# design.net
KiCad netlist of a schematic drawn in EasyEDA Pro
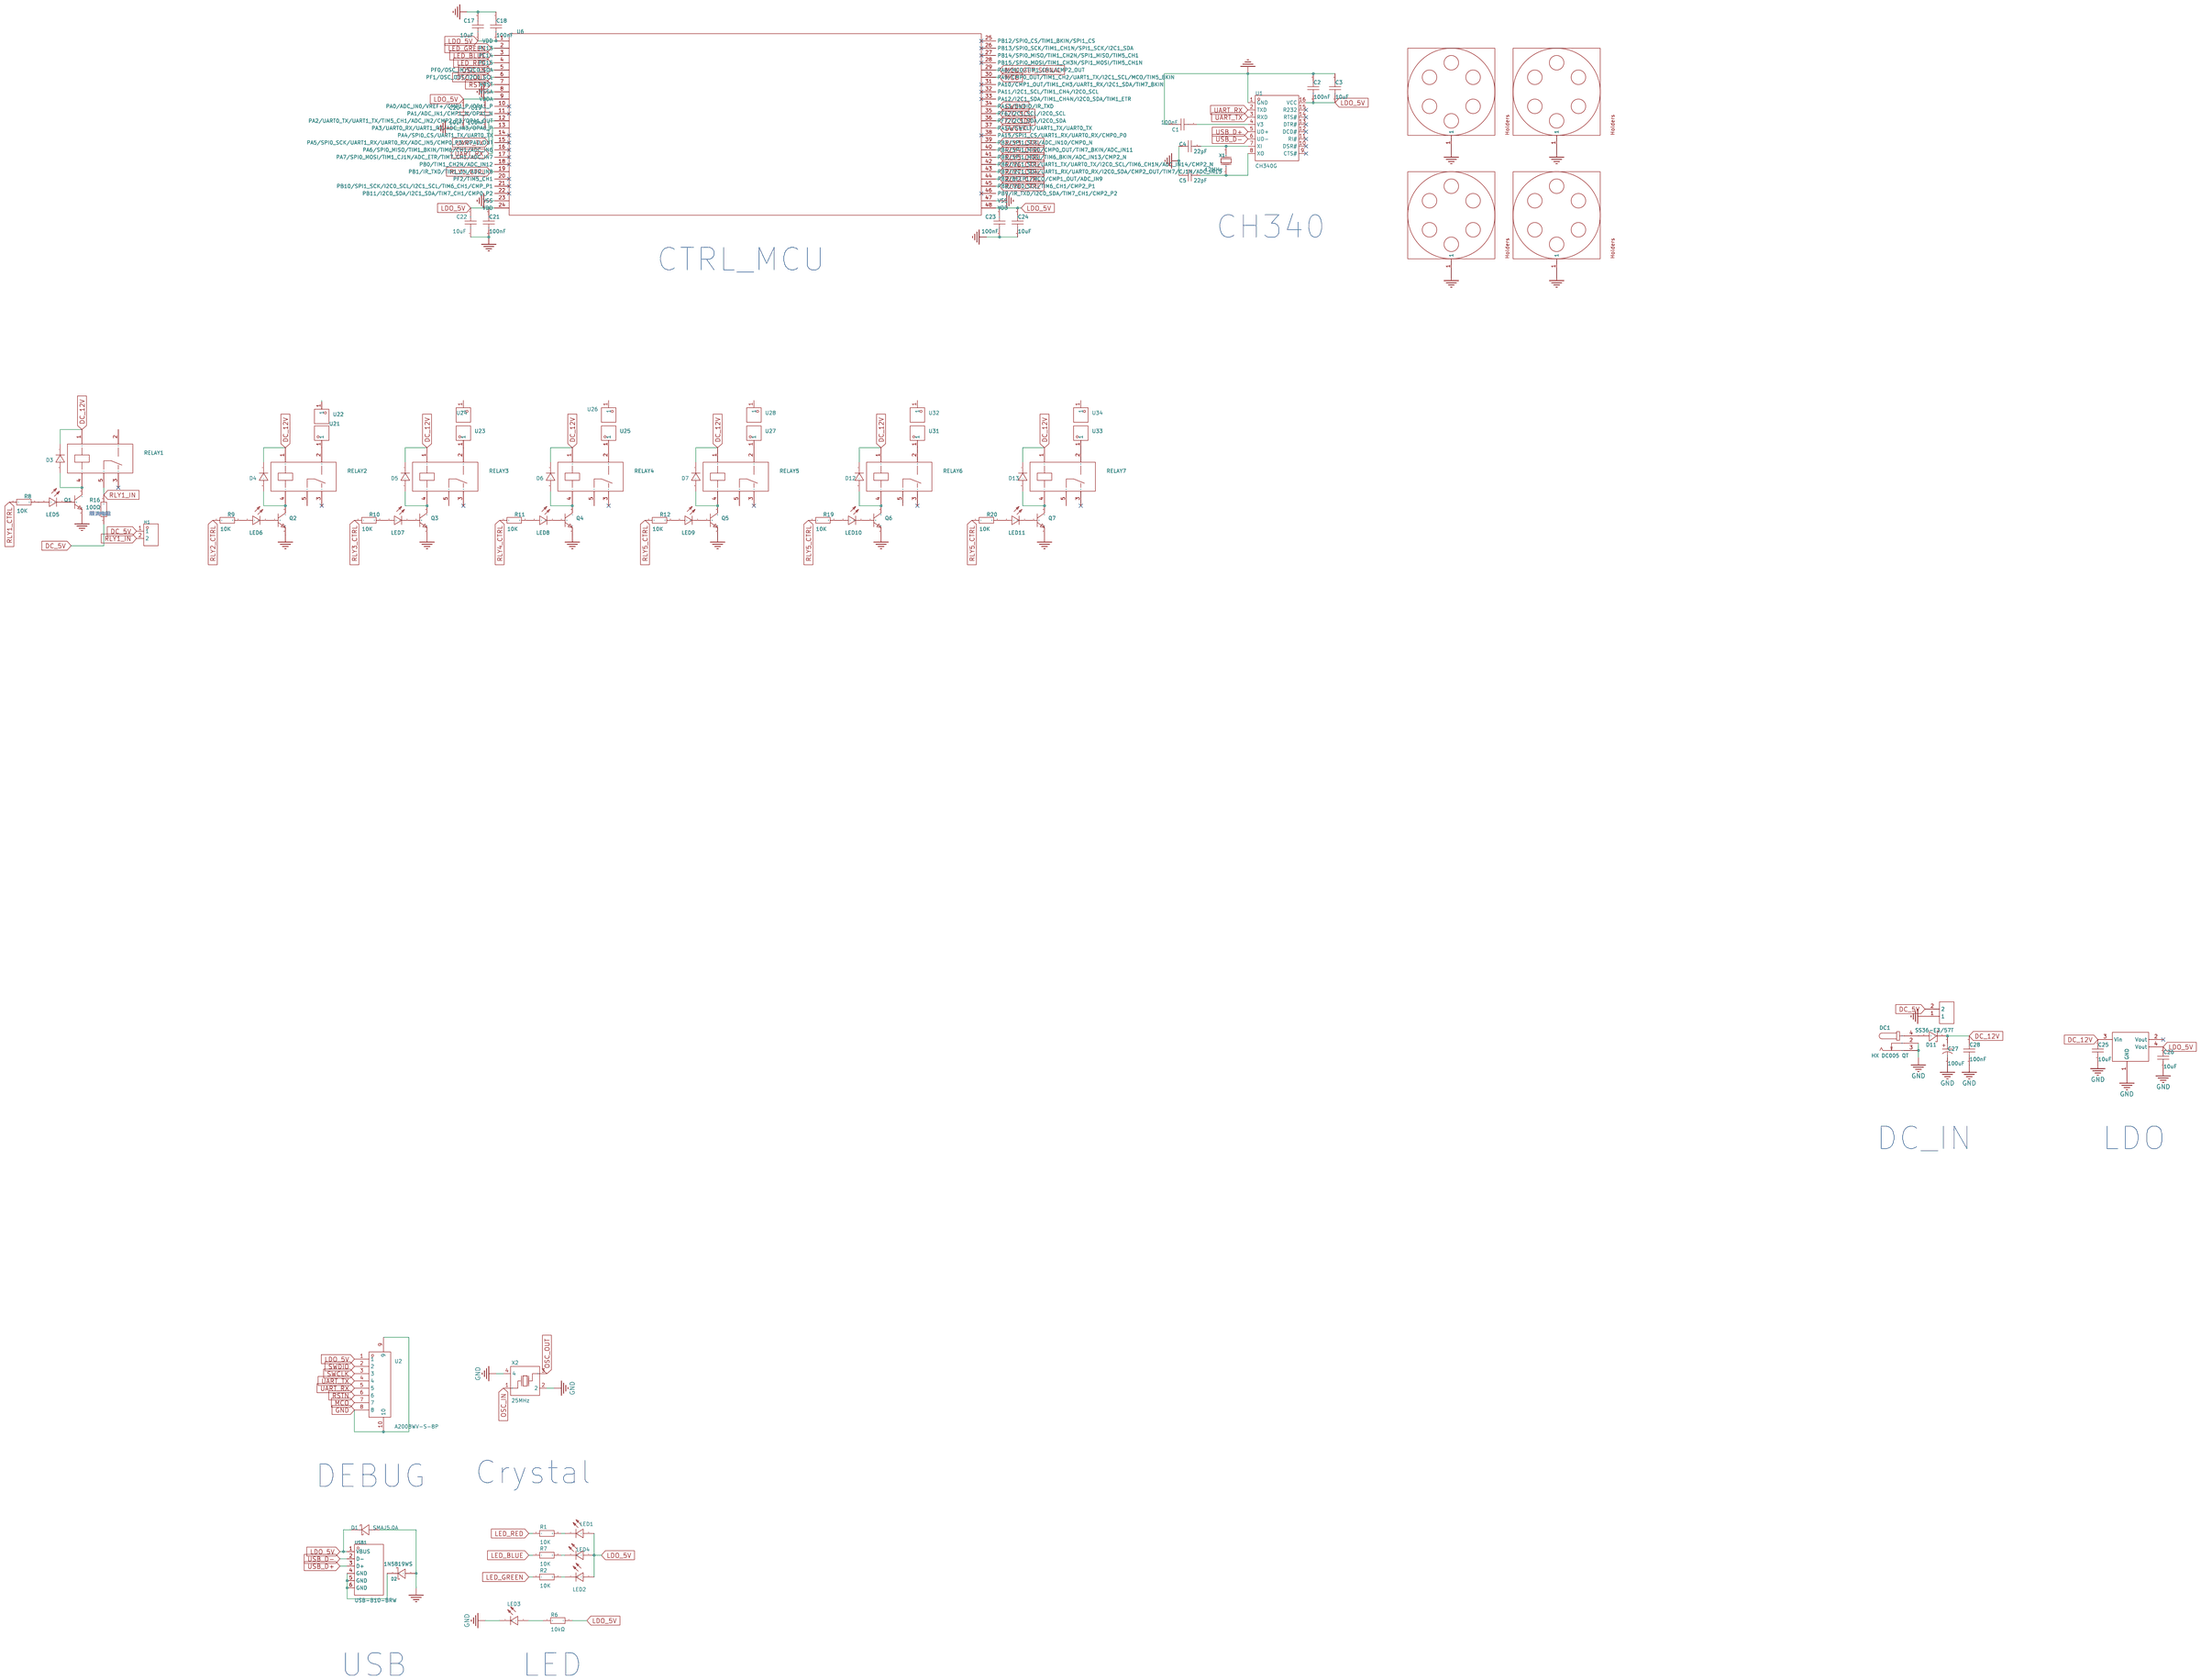
[diagram p0: P1]
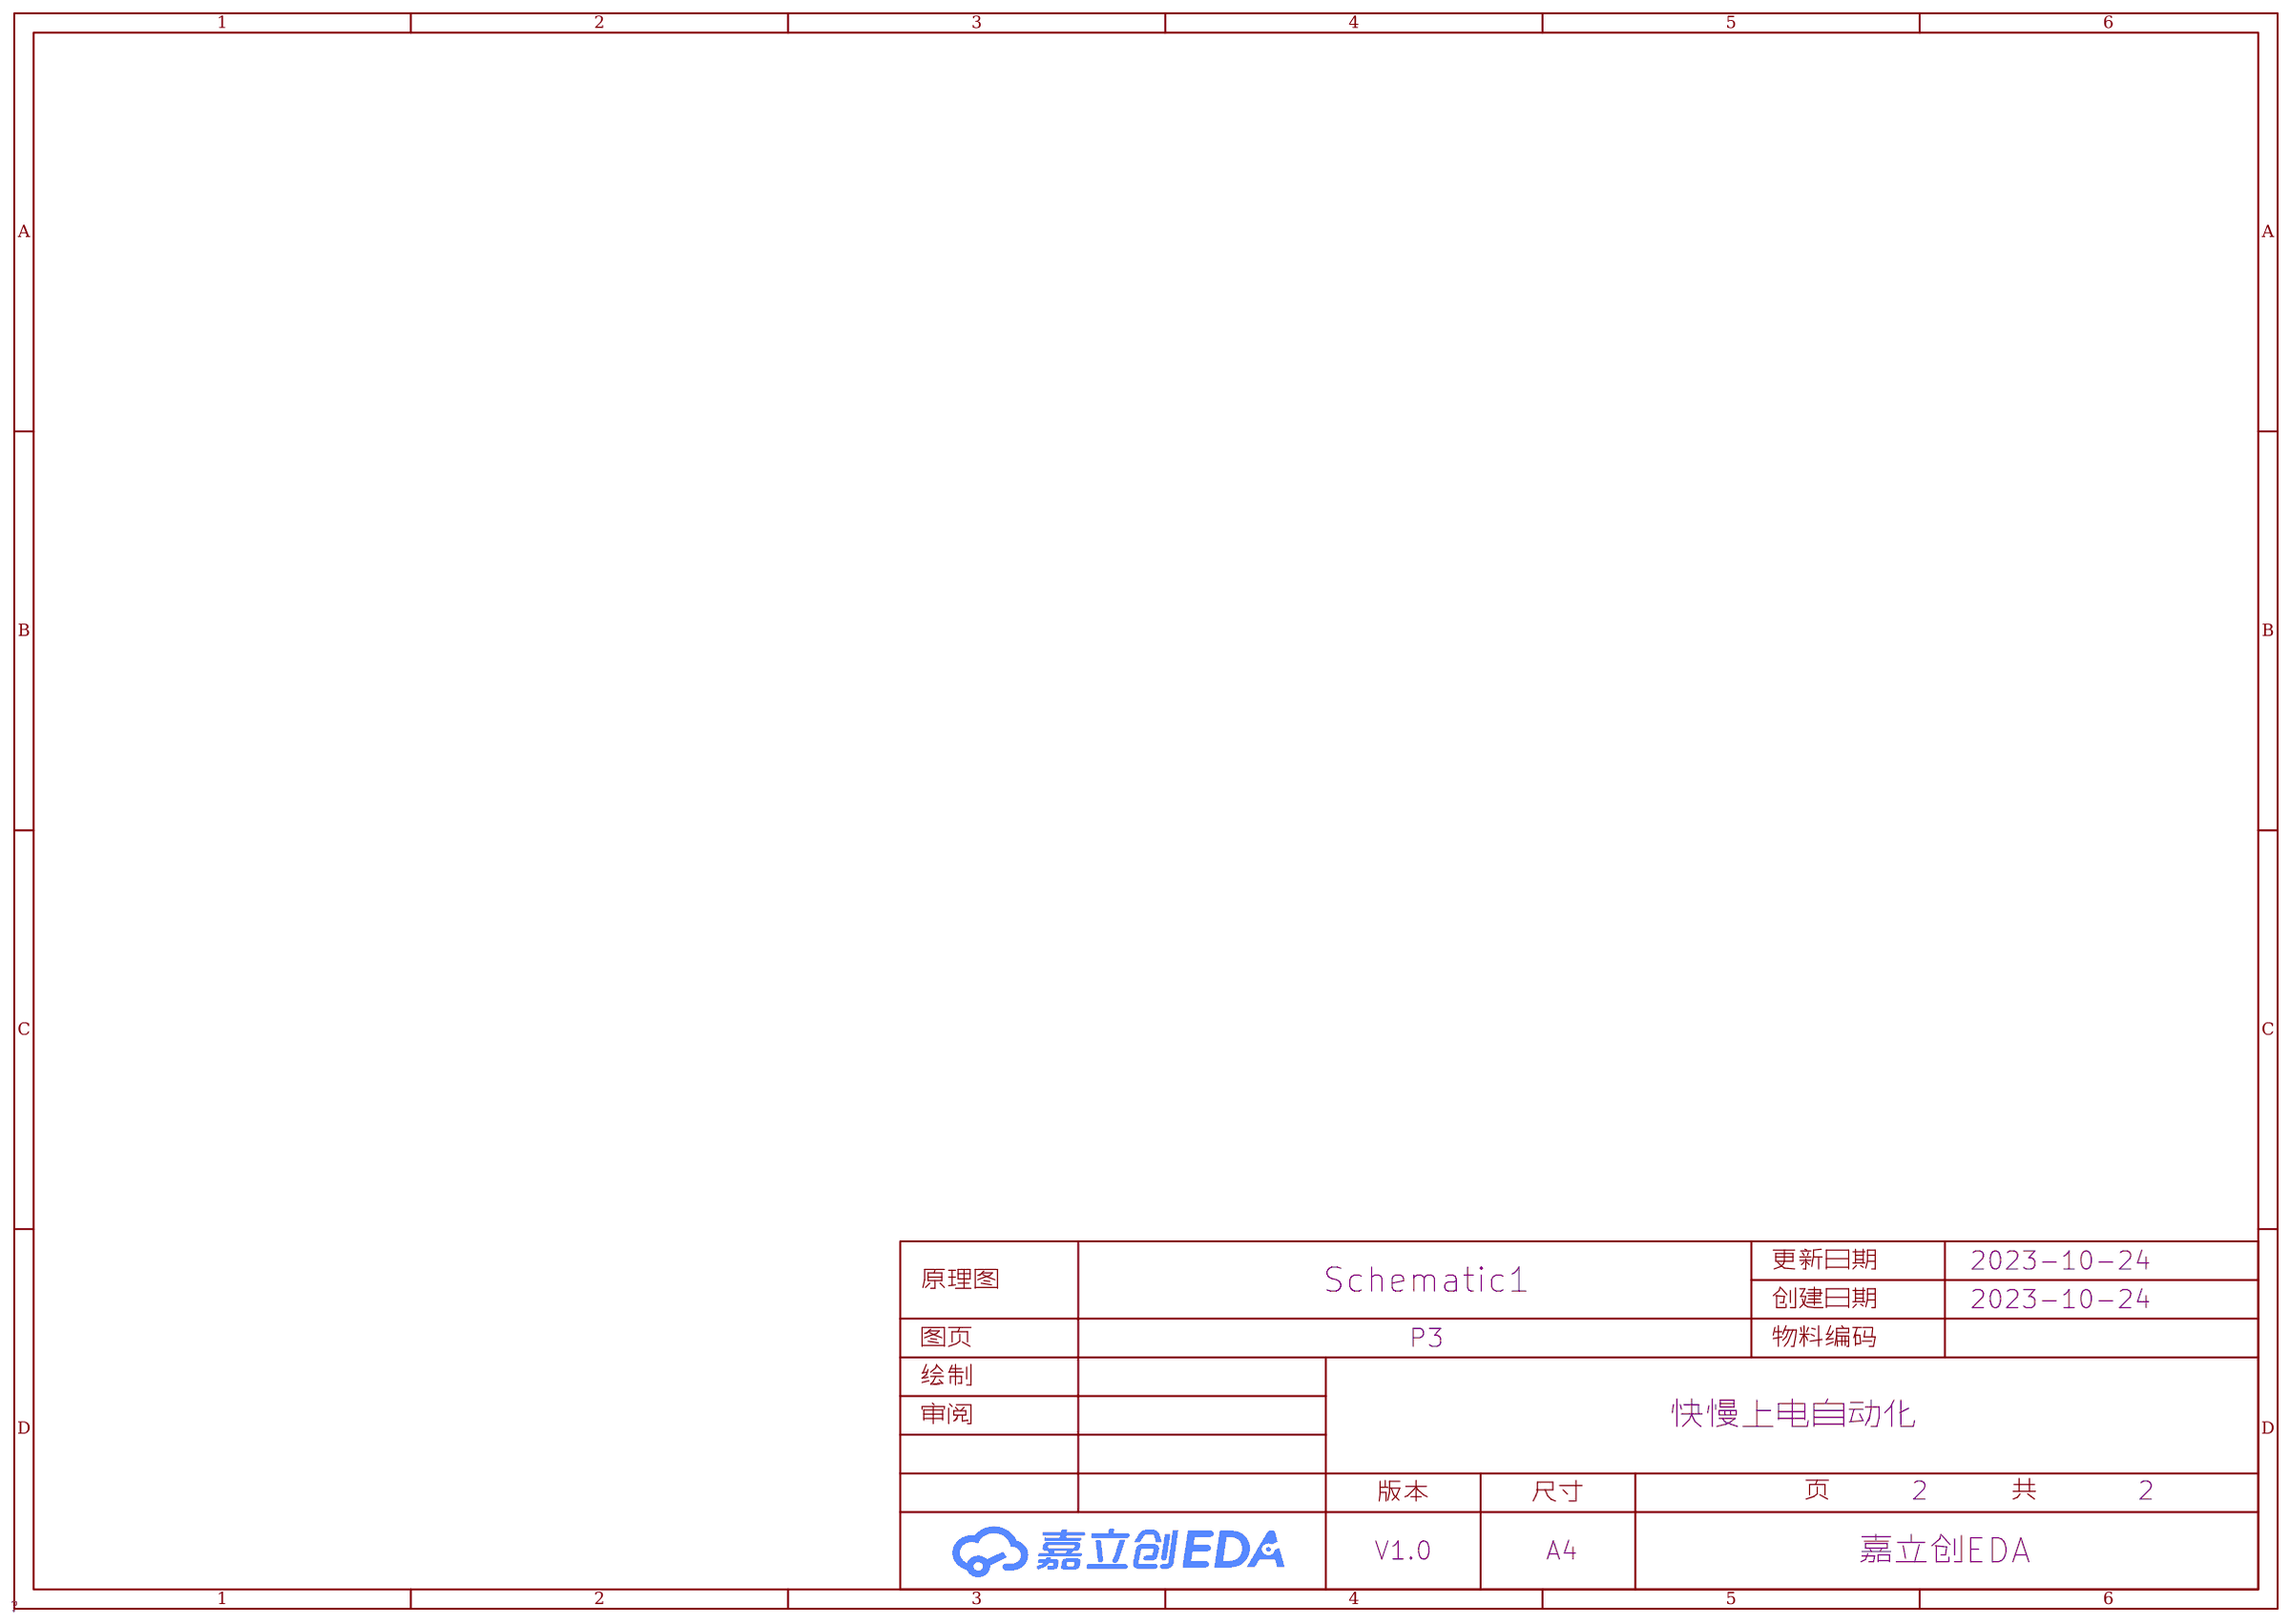
[diagram p1: P3]

(export (version "E")
  (design (tool "Eeschema 10.0.6"))
  (components
    (comp (ref "C1")
      (value "100nF")
      (footprint "easyedapro:C0603")
      (description "容值:100nF;精度:±10%;额定电压:50V;材质(温度系数):X7R;")
      (fields
        (field (name "Manufacturer Part") "CC0603KRX7R9BB104")
        (field (name "Manufacturer") "YAGEO(国巨)")
      )
      (libsource (lib "easyedapro") (part "CC0603KRX7R9BB104"))
    )
    (comp (ref "C2")
      (value "100nF")
      (footprint "easyedapro:C0603")
      (description "容值:100nF;精度:±10%;额定电压:50V;材质(温度系数):X7R;")
      (fields
        (field (name "Manufacturer Part") "CC0603KRX7R9BB104")
        (field (name "Manufacturer") "YAGEO(国巨)")
      )
      (libsource (lib "easyedapro") (part "CC0603KRX7R9BB104"))
    )
    (comp (ref "C3")
      (value "10uF")
      (footprint "easyedapro:C0603")
      (description "容值:10uF;精度:±10%;额定电压:10V;材质(温度系数):X5R;")
      (fields
        (field (name "Manufacturer Part") "CL10A106KP8NNNC")
        (field (name "Manufacturer") "SAMSUNG(三星)")
      )
      (libsource (lib "easyedapro") (part "CL10A106KP8NNNC"))
    )
    (comp (ref "C4")
      (value "22pF")
      (footprint "easyedapro:C0603")
      (description "容值:22pF;精度:±5%;额定电压:50V;材质(温度系数):C0G;")
      (fields
        (field (name "Manufacturer Part") "CL10C220JB8NNNC")
        (field (name "Manufacturer") "SAMSUNG(三星)")
      )
      (libsource (lib "easyedapro") (part "CL10C220JB8NNNC"))
    )
    (comp (ref "C5")
      (value "22pF")
      (footprint "easyedapro:C0603")
      (description "容值:22pF;精度:±5%;额定电压:50V;材质(温度系数):C0G;")
      (fields
        (field (name "Manufacturer Part") "CL10C220JB8NNNC")
        (field (name "Manufacturer") "SAMSUNG(三星)")
      )
      (libsource (lib "easyedapro") (part "CL10C220JB8NNNC"))
    )
    (comp (ref "C17")
      (value "10uF")
      (footprint "easyedapro:C0603")
      (description "容值:10uF;精度:±10%;额定电压:10V;材质(温度系数):X5R;")
      (fields
        (field (name "Manufacturer Part") "CL10A106KP8NNNC")
        (field (name "Manufacturer") "SAMSUNG(三星)")
      )
      (libsource (lib "easyedapro") (part "CL10A106KP8NNNC"))
    )
    (comp (ref "C18")
      (value "100nF")
      (footprint "easyedapro:C0603")
      (description "容值:100nF;精度:±10%;额定电压:50V;材质(温度系数):X7R;")
      (fields
        (field (name "Manufacturer Part") "CC0603KRX7R9BB104")
        (field (name "Manufacturer") "YAGEO(国巨)")
      )
      (libsource (lib "easyedapro") (part "CC0603KRX7R9BB104"))
    )
    (comp (ref "C19")
      (value "100nF")
      (footprint "easyedapro:C0603")
      (description "容值:100nF;精度:±10%;额定电压:50V;材质(温度系数):X7R;")
      (fields
        (field (name "Manufacturer Part") "CC0603KRX7R9BB104")
        (field (name "Manufacturer") "YAGEO(国巨)")
      )
      (libsource (lib "easyedapro") (part "CC0603KRX7R9BB104"))
    )
    (comp (ref "C20")
      (value "10uF")
      (footprint "easyedapro:C0603")
      (description "容值:10uF;精度:±10%;额定电压:10V;材质(温度系数):X5R;")
      (fields
        (field (name "Manufacturer Part") "CL10A106KP8NNNC")
        (field (name "Manufacturer") "SAMSUNG(三星)")
      )
      (libsource (lib "easyedapro") (part "CL10A106KP8NNNC"))
    )
    (comp (ref "C21")
      (value "100nF")
      (footprint "easyedapro:C0603")
      (description "容值:100nF;精度:±10%;额定电压:50V;材质(温度系数):X7R;")
      (fields
        (field (name "Manufacturer Part") "CC0603KRX7R9BB104")
        (field (name "Manufacturer") "YAGEO(国巨)")
      )
      (libsource (lib "easyedapro") (part "CC0603KRX7R9BB104"))
    )
    (comp (ref "C22")
      (value "10uF")
      (footprint "easyedapro:C0603")
      (description "容值:10uF;精度:±10%;额定电压:10V;材质(温度系数):X5R;")
      (fields
        (field (name "Manufacturer Part") "CL10A106KP8NNNC")
        (field (name "Manufacturer") "SAMSUNG(三星)")
      )
      (libsource (lib "easyedapro") (part "CL10A106KP8NNNC"))
    )
    (comp (ref "C23")
      (value "100nF")
      (footprint "easyedapro:C0603")
      (description "容值:100nF;精度:±10%;额定电压:50V;材质(温度系数):X7R;")
      (fields
        (field (name "Manufacturer Part") "CC0603KRX7R9BB104")
        (field (name "Manufacturer") "YAGEO(国巨)")
      )
      (libsource (lib "easyedapro") (part "CC0603KRX7R9BB104"))
    )
    (comp (ref "C24")
      (value "10uF")
      (footprint "easyedapro:C0603")
      (description "容值:10uF;精度:±10%;额定电压:10V;材质(温度系数):X5R;")
      (fields
        (field (name "Manufacturer Part") "CL10A106KP8NNNC")
        (field (name "Manufacturer") "SAMSUNG(三星)")
      )
      (libsource (lib "easyedapro") (part "CL10A106KP8NNNC"))
    )
    (comp (ref "C25")
      (value "10uF")
      (footprint "easyedapro:C1206")
      (description "容值:10uF;精度:±10%;额定电压:50V;材质(温度系数):X5R;")
      (fields
        (field (name "Manufacturer Part") "CL31A106KBHNNNE")
        (field (name "Manufacturer") "SAMSUNG(三星)")
      )
      (libsource (lib "easyedapro") (part "CL31A106KBHNNNE"))
    )
    (comp (ref "C26")
      (value "10uF")
      (footprint "easyedapro:C1206")
      (description "容值:10uF;精度:±10%;额定电压:50V;材质(温度系数):X5R;")
      (fields
        (field (name "Manufacturer Part") "CL31A106KBHNNNE")
        (field (name "Manufacturer") "SAMSUNG(三星)")
      )
      (libsource (lib "easyedapro") (part "CL31A106KBHNNNE"))
    )
    (comp (ref "C27")
      (value "100uF")
      (footprint "easyedapro:CAP-SMD_BD6.3-L6.6-W6.6-LS7.6-FD-1")
      (description "容值:100uF;额定电压:35V;电容体直径:-;电容体长度:-;纹波电流:-;等效串联电阻:-;工作寿命:-;")
      (fields
        (field (name "Manufacturer Part") "RVE100UF35V67RV0072")
        (field (name "Manufacturer") "KNSCHA(科尼盛)")
      )
      (libsource (lib "easyedapro") (part "RVE100UF35V67RV0072"))
    )
    (comp (ref "C28")
      (value "100nF")
      (footprint "easyedapro:C0603")
      (description "容值:100nF;精度:±10%;额定电压:50V;材质(温度系数):X7R;")
      (fields
        (field (name "Manufacturer Part") "CL10B104KB8NNNC")
        (field (name "Manufacturer") "SAMSUNG(三星)")
      )
      (libsource (lib "easyedapro") (part "CL10B104KB8NNNC"))
    )
    (comp (ref "D1")
      (value "SMAJ5.0A")
      (footprint "easyedapro:SMA_L4.3-W2.6-LS5.0-RD")
      (description "极性:单向;反向截止电压(Vrwm):5V;击穿电压:6.4V;最大钳位电压:9.2V;")
      (fields (field (name "Manufacturer") "Liown(里阳半导体)"))
      (libsource (lib "easyedapro") (part "SMAJ5.0A_C2925443"))
    )
    (comp (ref "D2")
      (value "1N5819WS")
      (footprint "easyedapro:SOD-323_L1.8-W1.3-LS2.5-RD")
      (description "直流反向耐压(Vr):40V;平均整流电流(Io):1A;正向压降(Vf):600mV@1A;")
      (fields (field (name "Manufacturer") "Hottech(合科泰)"))
      (libsource (lib "easyedapro") (part "1N5819WS"))
    )
    (comp (ref "D3")
      (value "1N4148WS")
      (footprint "easyedapro:SOD-323_L1.8-W1.3-LS2.5-RD")
      (description "二极管配置:独立式;功率:200mW;直流反向耐压(Vr):100V;平均整流电流(Io):150mA;正向压降(Vf):1.25V@150mA;反向恢复时间(trr):4ns;")
      (fields (field (name "Manufacturer") "CJ(江苏长电/长晶)"))
      (libsource (lib "easyedapro") (part "1N4148WS T4"))
    )
    (comp (ref "D4")
      (value "1N4148WS")
      (footprint "easyedapro:SOD-323_L1.8-W1.3-LS2.5-RD")
      (description "二极管配置:独立式;功率:200mW;直流反向耐压(Vr):100V;平均整流电流(Io):150mA;正向压降(Vf):1.25V@150mA;反向恢复时间(trr):4ns;")
      (fields (field (name "Manufacturer") "CJ(江苏长电/长晶)"))
      (libsource (lib "easyedapro") (part "1N4148WS T4"))
    )
    (comp (ref "D5")
      (value "1N4148WS")
      (footprint "easyedapro:SOD-323_L1.8-W1.3-LS2.5-RD")
      (description "二极管配置:独立式;功率:200mW;直流反向耐压(Vr):100V;平均整流电流(Io):150mA;正向压降(Vf):1.25V@150mA;反向恢复时间(trr):4ns;")
      (fields (field (name "Manufacturer") "CJ(江苏长电/长晶)"))
      (libsource (lib "easyedapro") (part "1N4148WS T4"))
    )
    (comp (ref "D6")
      (value "1N4148WS")
      (footprint "easyedapro:SOD-323_L1.8-W1.3-LS2.5-RD")
      (description "二极管配置:独立式;功率:200mW;直流反向耐压(Vr):100V;平均整流电流(Io):150mA;正向压降(Vf):1.25V@150mA;反向恢复时间(trr):4ns;")
      (fields (field (name "Manufacturer") "CJ(江苏长电/长晶)"))
      (libsource (lib "easyedapro") (part "1N4148WS T4"))
    )
    (comp (ref "D7")
      (value "1N4148WS")
      (footprint "easyedapro:SOD-323_L1.8-W1.3-LS2.5-RD")
      (description "二极管配置:独立式;功率:200mW;直流反向耐压(Vr):100V;平均整流电流(Io):150mA;正向压降(Vf):1.25V@150mA;反向恢复时间(trr):4ns;")
      (fields (field (name "Manufacturer") "CJ(江苏长电/长晶)"))
      (libsource (lib "easyedapro") (part "1N4148WS T4"))
    )
    (comp (ref "D11")
      (value "SS36-E3/57T")
      (footprint "easyedapro:SMC_L7.1-W6.2-LS8.1-R-RD")
      (description "直流反向耐压（Vr）:60V;平均整流电流（Io）:3A;正向压降（Vf）:750mV @ 3A;")
      (fields (field (name "Manufacturer") "VISHAY(威世)"))
      (libsource (lib "easyedapro") (part "SS36-E3/57T"))
    )
    (comp (ref "D12")
      (value "1N4148WS")
      (footprint "easyedapro:SOD-323_L1.8-W1.3-LS2.5-RD")
      (description "二极管配置:独立式;功率:200mW;直流反向耐压(Vr):100V;平均整流电流(Io):150mA;正向压降(Vf):1.25V@150mA;反向恢复时间(trr):4ns;")
      (fields (field (name "Manufacturer") "CJ(江苏长电/长晶)"))
      (libsource (lib "easyedapro") (part "1N4148WS T4"))
    )
    (comp (ref "D13")
      (value "1N4148WS")
      (footprint "easyedapro:SOD-323_L1.8-W1.3-LS2.5-RD")
      (description "二极管配置:独立式;功率:200mW;直流反向耐压(Vr):100V;平均整流电流(Io):150mA;正向压降(Vf):1.25V@150mA;反向恢复时间(trr):4ns;")
      (fields (field (name "Manufacturer") "CJ(江苏长电/长晶)"))
      (libsource (lib "easyedapro") (part "1N4148WS T4"))
    )
    (comp (ref "DC1")
      (value "HX DC005 QT")
      (footprint "easyedapro:DC-IN-TH_HANXIA_HX-DC005-QT")
      (description "连接器类型:DC插座;安装方式:卧插;额定电流:1A;额定电压:12V;工作温度范围:-25°C~+85°C;")
      (fields (field (name "Manufacturer") "hanxia(韩下)"))
      (libsource (lib "easyedapro") (part "HX DC005 QT"))
    )
    (comp (ref "H1")
      (value "PZ254V-11-02P")
      (footprint "easyedapro:HDR-TH_2P-P2.54-V-M")
      (fields (field (name "Manufacturer") "XFCN(兴飞)"))
      (libsource (lib "easyedapro") (part "PZ254V-11-02P"))
    )
    (comp (ref "J2")
      (value "~")
      (footprint "easyedapro:DEMO板安装孔")
      (libsource (lib "easyedapro") (part "螺孔_3.1X6MM"))
    )
    (comp (ref "J3")
      (value "~")
      (footprint "easyedapro:DEMO板安装孔")
      (libsource (lib "easyedapro") (part "螺孔_3.1X6MM"))
    )
    (comp (ref "J4")
      (value "~")
      (footprint "easyedapro:DEMO板安装孔")
      (libsource (lib "easyedapro") (part "螺孔_3.1X6MM"))
    )
    (comp (ref "J5")
      (value "~")
      (footprint "easyedapro:DEMO板安装孔")
      (libsource (lib "easyedapro") (part "螺孔_3.1X6MM"))
    )
    (comp (ref "LED1")
      (value "NCD0603R1")
      (footprint "easyedapro:LED0603-RD_RED")
      (description "发光颜色:红灯;")
      (fields (field (name "Manufacturer") "国星光电"))
      (libsource (lib "easyedapro") (part "FC-DA1608HRK-620D"))
    )
    (comp (ref "LED2")
      (value "19-217/GHC-YR1S2/3T")
      (footprint "easyedapro:LED0603-RD")
      (fields (field (name "Manufacturer") "EVERLIGHT(亿光)"))
      (libsource (lib "easyedapro") (part "19-217/GHC-YR1S2/3T"))
    )
    (comp (ref "LED3")
      (value "19-217/GHC-YR1S2/3T")
      (footprint "easyedapro:LED0603-RD")
      (fields (field (name "Manufacturer") "EVERLIGHT(亿光)"))
      (libsource (lib "easyedapro") (part "19-217/GHC-YR1S2/3T"))
    )
    (comp (ref "LED4")
      (value "19-217/BHC-ZL1M2RY/3T")
      (footprint "easyedapro:LED0603-FD_BLUE")
      (description "发光颜色:蓝灯;二极管配置:-;主波长:465nm~475nm;色温:-;功率:110mW;安装方式:-;")
      (fields (field (name "Manufacturer") "EVERLIGHT(亿光)"))
      (libsource (lib "easyedapro") (part "19-217/BHC-ZL1M2RY/3T"))
    )
    (comp (ref "LED5")
      (value "19-217/GHC-YR1S2/3T")
      (footprint "easyedapro:LED0603-RD")
      (fields (field (name "Manufacturer") "EVERLIGHT(亿光)"))
      (libsource (lib "easyedapro") (part "19-217/GHC-YR1S2/3T"))
    )
    (comp (ref "LED6")
      (value "19-217/GHC-YR1S2/3T")
      (footprint "easyedapro:LED0603-RD")
      (fields (field (name "Manufacturer") "EVERLIGHT(亿光)"))
      (libsource (lib "easyedapro") (part "19-217/GHC-YR1S2/3T"))
    )
    (comp (ref "LED7")
      (value "19-217/GHC-YR1S2/3T")
      (footprint "easyedapro:LED0603-RD")
      (fields (field (name "Manufacturer") "EVERLIGHT(亿光)"))
      (libsource (lib "easyedapro") (part "19-217/GHC-YR1S2/3T"))
    )
    (comp (ref "LED8")
      (value "19-217/GHC-YR1S2/3T")
      (footprint "easyedapro:LED0603-RD")
      (fields (field (name "Manufacturer") "EVERLIGHT(亿光)"))
      (libsource (lib "easyedapro") (part "19-217/GHC-YR1S2/3T"))
    )
    (comp (ref "LED9")
      (value "19-217/GHC-YR1S2/3T")
      (footprint "easyedapro:LED0603-RD")
      (fields (field (name "Manufacturer") "EVERLIGHT(亿光)"))
      (libsource (lib "easyedapro") (part "19-217/GHC-YR1S2/3T"))
    )
    (comp (ref "LED10")
      (value "19-217/GHC-YR1S2/3T")
      (footprint "easyedapro:LED0603-RD")
      (fields (field (name "Manufacturer") "EVERLIGHT(亿光)"))
      (libsource (lib "easyedapro") (part "19-217/GHC-YR1S2/3T"))
    )
    (comp (ref "LED11")
      (value "19-217/GHC-YR1S2/3T")
      (footprint "easyedapro:LED0603-RD")
      (fields (field (name "Manufacturer") "EVERLIGHT(亿光)"))
      (libsource (lib "easyedapro") (part "19-217/GHC-YR1S2/3T"))
    )
    (comp (ref "P1")
      (value "WJ500V-5.08-2P")
      (footprint "easyedapro:CONN-TH_2P-P5.00_WJ500V-5.08-2P")
      (fields (field (name "Manufacturer") "KANGNEX(康奈克斯电气)"))
      (libsource (lib "easyedapro") (part "WJ500V-5.08-2P-14-00A"))
    )
    (comp (ref "Q1")
      (value "SS8050")
      (footprint "easyedapro:SOT-23-3_L2.9-W1.3-P1.90-LS2.4-BR")
      (description "晶体管类型:NPN;集射极击穿电压(Vceo):25V;集电极电流(Ic):1.5A;功率(Pd):300mW;直流电流增益(hFE@Ic,Vce):200@100mA,1V;")
      (fields (field (name "Manufacturer") "CJ(江苏长电/长晶)"))
      (libsource (lib "easyedapro") (part "SS8050_C2150"))
    )
    (comp (ref "Q2")
      (value "SS8050")
      (footprint "easyedapro:SOT-23-3_L2.9-W1.3-P1.90-LS2.4-BR")
      (description "晶体管类型:NPN;集射极击穿电压(Vceo):25V;集电极电流(Ic):1.5A;功率(Pd):300mW;直流电流增益(hFE@Ic,Vce):200@100mA,1V;")
      (fields (field (name "Manufacturer") "CJ(江苏长电/长晶)"))
      (libsource (lib "easyedapro") (part "SS8050_C2150"))
    )
    (comp (ref "Q3")
      (value "SS8050")
      (footprint "easyedapro:SOT-23-3_L2.9-W1.3-P1.90-LS2.4-BR")
      (description "晶体管类型:NPN;集射极击穿电压(Vceo):25V;集电极电流(Ic):1.5A;功率(Pd):300mW;直流电流增益(hFE@Ic,Vce):200@100mA,1V;")
      (fields (field (name "Manufacturer") "CJ(江苏长电/长晶)"))
      (libsource (lib "easyedapro") (part "SS8050_C2150"))
    )
    (comp (ref "Q4")
      (value "SS8050")
      (footprint "easyedapro:SOT-23-3_L2.9-W1.3-P1.90-LS2.4-BR")
      (description "晶体管类型:NPN;集射极击穿电压(Vceo):25V;集电极电流(Ic):1.5A;功率(Pd):300mW;直流电流增益(hFE@Ic,Vce):200@100mA,1V;")
      (fields (field (name "Manufacturer") "CJ(江苏长电/长晶)"))
      (libsource (lib "easyedapro") (part "SS8050_C2150"))
    )
    (comp (ref "Q5")
      (value "SS8050")
      (footprint "easyedapro:SOT-23-3_L2.9-W1.3-P1.90-LS2.4-BR")
      (description "晶体管类型:NPN;集射极击穿电压(Vceo):25V;集电极电流(Ic):1.5A;功率(Pd):300mW;直流电流增益(hFE@Ic,Vce):200@100mA,1V;")
      (fields (field (name "Manufacturer") "CJ(江苏长电/长晶)"))
      (libsource (lib "easyedapro") (part "SS8050_C2150"))
    )
    (comp (ref "Q6")
      (value "SS8050")
      (footprint "easyedapro:SOT-23-3_L2.9-W1.3-P1.90-LS2.4-BR")
      (description "晶体管类型:NPN;集射极击穿电压(Vceo):25V;集电极电流(Ic):1.5A;功率(Pd):300mW;直流电流增益(hFE@Ic,Vce):200@100mA,1V;")
      (fields (field (name "Manufacturer") "CJ(江苏长电/长晶)"))
      (libsource (lib "easyedapro") (part "SS8050_C2150"))
    )
    (comp (ref "Q7")
      (value "SS8050")
      (footprint "easyedapro:SOT-23-3_L2.9-W1.3-P1.90-LS2.4-BR")
      (description "晶体管类型:NPN;集射极击穿电压(Vceo):25V;集电极电流(Ic):1.5A;功率(Pd):300mW;直流电流增益(hFE@Ic,Vce):200@100mA,1V;")
      (fields (field (name "Manufacturer") "CJ(江苏长电/长晶)"))
      (libsource (lib "easyedapro") (part "SS8050_C2150"))
    )
    (comp (ref "R1") (value "10K") (footprint "easyedapro:R0603") (libsource (lib "easyedapro") (part "电阻")))
    (comp (ref "R2") (value "10K") (footprint "easyedapro:R0603") (libsource (lib "easyedapro") (part "电阻")))
    (comp (ref "R6")
      (value "10kΩ")
      (footprint "easyedapro:R0603")
      (description "电阻类型:厚膜电阻;阻值:10kΩ;精度:±1%;功率:100mW;温度系数:±100ppm/°C;最大工作电压:75V;工作温度范围:-55°C~+155°C;")
      (fields
        (field (name "Manufacturer Part") "0603WAF1002T5E")
        (field (name "Manufacturer") "UNI-ROYAL(厚声)")
      )
      (libsource (lib "easyedapro") (part "0603WAF1002T5E"))
    )
    (comp (ref "R7") (value "10K") (footprint "easyedapro:R0603") (libsource (lib "easyedapro") (part "电阻")))
    (comp (ref "R8") (value "10K") (footprint "easyedapro:R0603") (libsource (lib "easyedapro") (part "电阻")))
    (comp (ref "R9") (value "10K") (footprint "easyedapro:R0603") (libsource (lib "easyedapro") (part "电阻")))
    (comp (ref "R10") (value "10K") (footprint "easyedapro:R0603") (libsource (lib "easyedapro") (part "电阻")))
    (comp (ref "R11") (value "10K") (footprint "easyedapro:R0603") (libsource (lib "easyedapro") (part "电阻")))
    (comp (ref "R12") (value "10K") (footprint "easyedapro:R0603") (libsource (lib "easyedapro") (part "电阻")))
    (comp (ref "R16")
      (value "100Ω")
      (footprint "easyedapro:R0805")
      (description "电阻类型:厚膜电阻;阻值:100Ω;精度:±1%;功率:125mW;")
      (fields
        (field (name "Manufacturer Part") "0805W8F1000T5E")
        (field (name "Manufacturer") "UNI-ROYAL(厚声)")
      )
      (libsource (lib "easyedapro") (part "0805W8F1000T5E"))
    )
    (comp (ref "R19") (value "10K") (footprint "easyedapro:R0603") (libsource (lib "easyedapro") (part "电阻")))
    (comp (ref "R20") (value "10K") (footprint "easyedapro:R0603") (libsource (lib "easyedapro") (part "电阻")))
    (comp (ref "RELAY1")
      (value "SRD-12VDC-SL-C")
      (footprint "easyedapro:RELAY-TH_SRD-XXVDC-XL-C")
      (description "线圈电压:12V;引脚数:5;触点形式:一组转换:1C(单刀双掷-转换);触点容量(电阻负载):-;")
      (fields (field (name "Manufacturer") "松乐"))
      (libsource (lib "easyedapro") (part "SRD-12VDC-SL-C"))
    )
    (comp (ref "RELAY2")
      (value "SRD-12VDC-SL-C")
      (footprint "easyedapro:RELAY-TH_SRD-XXVDC-XL-C")
      (description "线圈电压:12V;引脚数:5;触点形式:一组转换:1C(单刀双掷-转换);触点容量(电阻负载):-;")
      (fields (field (name "Manufacturer") "松乐"))
      (libsource (lib "easyedapro") (part "SRD-12VDC-SL-C"))
    )
    (comp (ref "RELAY3")
      (value "SRD-12VDC-SL-C")
      (footprint "easyedapro:RELAY-TH_SRD-XXVDC-XL-C")
      (description "线圈电压:12V;引脚数:5;触点形式:一组转换:1C(单刀双掷-转换);触点容量(电阻负载):-;")
      (fields (field (name "Manufacturer") "松乐"))
      (libsource (lib "easyedapro") (part "SRD-12VDC-SL-C"))
    )
    (comp (ref "RELAY4")
      (value "SRD-12VDC-SL-C")
      (footprint "easyedapro:RELAY-TH_SRD-XXVDC-XL-C")
      (description "线圈电压:12V;引脚数:5;触点形式:一组转换:1C(单刀双掷-转换);触点容量(电阻负载):-;")
      (fields (field (name "Manufacturer") "松乐"))
      (libsource (lib "easyedapro") (part "SRD-12VDC-SL-C"))
    )
    (comp (ref "RELAY5")
      (value "SRD-12VDC-SL-C")
      (footprint "easyedapro:RELAY-TH_SRD-XXVDC-XL-C")
      (description "线圈电压:12V;引脚数:5;触点形式:一组转换:1C(单刀双掷-转换);触点容量(电阻负载):-;")
      (fields (field (name "Manufacturer") "松乐"))
      (libsource (lib "easyedapro") (part "SRD-12VDC-SL-C"))
    )
    (comp (ref "RELAY6")
      (value "SRD-12VDC-SL-C")
      (footprint "easyedapro:RELAY-TH_SRD-XXVDC-XL-C")
      (description "线圈电压:12V;引脚数:5;触点形式:一组转换:1C(单刀双掷-转换);触点容量(电阻负载):-;")
      (fields (field (name "Manufacturer") "松乐"))
      (libsource (lib "easyedapro") (part "SRD-12VDC-SL-C"))
    )
    (comp (ref "RELAY7")
      (value "SRD-12VDC-SL-C")
      (footprint "easyedapro:RELAY-TH_SRD-XXVDC-XL-C")
      (description "线圈电压:12V;引脚数:5;触点形式:一组转换:1C(单刀双掷-转换);触点容量(电阻负载):-;")
      (fields (field (name "Manufacturer") "松乐"))
      (libsource (lib "easyedapro") (part "SRD-12VDC-SL-C"))
    )
    (comp (ref "U1")
      (value "CH340G")
      (footprint "easyedapro:SOIC-16_L9.9-W3.9-P1.27-LS6.0-BL")
      (description "应用功能:Transceiver;接口协议:USB 2.0;数据速率:2Mbps;供电电压:3.3V；5V;")
      (fields (field (name "Manufacturer") "WCH(南京沁恒)"))
      (libsource (lib "easyedapro") (part "CH340G"))
    )
    (comp (ref "U2")
      (value "A2008WV-S-8P")
      (footprint "easyedapro:CONN-SMD_A2008WV-S-8P")
      (description "参考系列:PH;间距:2mm;插针结构:1x8P;排数:1;每排PIN数:8;行距:-;安装方式:-;触头材质:黄铜;")
      (fields (field (name "Manufacturer") "CJT(长江连接器)"))
      (libsource (lib "easyedapro") (part "A2008WV-S-8P"))
    )
    (comp (ref "U6") (value "PT32A030C8T7") (libsource (lib "easyedapro") (part "PT32A030C8T7")))
    (comp (ref "U21")
      (value "X5511FV-01-C30D97-0970")
      (footprint "easyedapro:HDR-TH_1P-V-F-1")
      (fields (field (name "Manufacturer") "XKB Connectivity(中国星坤)"))
      (libsource (lib "easyedapro") (part "X5511FV-01-C30D97-0970"))
    )
    (comp (ref "U22")
      (value "X5511FV-01-C30D97-0970")
      (footprint "easyedapro:HDR-TH_1P-V-F-1")
      (fields (field (name "Manufacturer") "XKB Connectivity(中国星坤)"))
      (libsource (lib "easyedapro") (part "X5511FV-01-C30D97-0970"))
    )
    (comp (ref "U23")
      (value "X5511FV-01-C30D97-0970")
      (footprint "easyedapro:HDR-TH_1P-V-F-1")
      (fields (field (name "Manufacturer") "XKB Connectivity(中国星坤)"))
      (libsource (lib "easyedapro") (part "X5511FV-01-C30D97-0970"))
    )
    (comp (ref "U24")
      (value "X5511FV-01-C30D97-0970")
      (footprint "easyedapro:HDR-TH_1P-V-F-1")
      (fields (field (name "Manufacturer") "XKB Connectivity(中国星坤)"))
      (libsource (lib "easyedapro") (part "X5511FV-01-C30D97-0970"))
    )
    (comp (ref "U25")
      (value "X5511FV-01-C30D97-0970")
      (footprint "easyedapro:HDR-TH_1P-V-F-1")
      (fields (field (name "Manufacturer") "XKB Connectivity(中国星坤)"))
      (libsource (lib "easyedapro") (part "X5511FV-01-C30D97-0970"))
    )
    (comp (ref "U26")
      (value "X5511FV-01-C30D97-0970")
      (footprint "easyedapro:HDR-TH_1P-V-F-1")
      (fields (field (name "Manufacturer") "XKB Connectivity(中国星坤)"))
      (libsource (lib "easyedapro") (part "X5511FV-01-C30D97-0970"))
    )
    (comp (ref "U27")
      (value "X5511FV-01-C30D97-0970")
      (footprint "easyedapro:HDR-TH_1P-V-F-1")
      (fields (field (name "Manufacturer") "XKB Connectivity(中国星坤)"))
      (libsource (lib "easyedapro") (part "X5511FV-01-C30D97-0970"))
    )
    (comp (ref "U28")
      (value "X5511FV-01-C30D97-0970")
      (footprint "easyedapro:HDR-TH_1P-V-F-1")
      (fields (field (name "Manufacturer") "XKB Connectivity(中国星坤)"))
      (libsource (lib "easyedapro") (part "X5511FV-01-C30D97-0970"))
    )
    (comp (ref "U30")
      (value "AMS1086CM-5.0")
      (footprint "easyedapro:TO-263-3_L8.6-W10.2-P2.54-LS14.4-TL")
      (description "输出类型:固定;输出极性:正;最大输入电压:15V;输出电压:5V;输出电流:1.5A;电源纹波抑制比(PSRR):68dB@(120Hz);")
      (fields (field (name "Manufacturer") "AMS"))
      (libsource (lib "easyedapro") (part "AMS1086CM-5.0"))
    )
    (comp (ref "U31")
      (value "X5511FV-01-C30D97-0970")
      (footprint "easyedapro:HDR-TH_1P-V-F-1")
      (fields (field (name "Manufacturer") "XKB Connectivity(中国星坤)"))
      (libsource (lib "easyedapro") (part "X5511FV-01-C30D97-0970"))
    )
    (comp (ref "U32")
      (value "X5511FV-01-C30D97-0970")
      (footprint "easyedapro:HDR-TH_1P-V-F-1")
      (fields (field (name "Manufacturer") "XKB Connectivity(中国星坤)"))
      (libsource (lib "easyedapro") (part "X5511FV-01-C30D97-0970"))
    )
    (comp (ref "U33")
      (value "X5511FV-01-C30D97-0970")
      (footprint "easyedapro:HDR-TH_1P-V-F-1")
      (fields (field (name "Manufacturer") "XKB Connectivity(中国星坤)"))
      (libsource (lib "easyedapro") (part "X5511FV-01-C30D97-0970"))
    )
    (comp (ref "U34")
      (value "X5511FV-01-C30D97-0970")
      (footprint "easyedapro:HDR-TH_1P-V-F-1")
      (fields (field (name "Manufacturer") "XKB Connectivity(中国星坤)"))
      (libsource (lib "easyedapro") (part "X5511FV-01-C30D97-0970"))
    )
    (comp (ref "USB1")
      (value "USB-B10-BRW")
      (footprint "easyedapro:USB-B-TH_USB-B10-BRW")
      (fields (field (name "Manufacturer") "XUNPU(讯普)"))
      (libsource (lib "easyedapro") (part "USB-B10-BRW"))
    )
    (comp (ref "X1")
      (value "12MHz")
      (footprint "easyedapro:HC-49US_L11.5-W4.5-P4.88")
      (description "频率:12MHz;频率公差:±20ppm;负载电容:20pF;")
      (fields (field (name "Manufacturer Part") "X49SD12MSD2SC") (field (name "Manufacturer") "YXC(扬兴晶振)"))
      (libsource (lib "easyedapro") (part "X49SD12MSD2SC"))
    )
    (comp (ref "X2")
      (value "25MHz")
      (footprint "easyedapro:OSC-SMD_4P-L2.5-W2.0-BL")
      (description "晶振类型:-;频率:25MHz;频率公差:±25ppm;频率稳定度:±50ppm;负载电容:10pF;等效串联电阻(ESR):60Ω;工作温度:-40°C~+125°C;")
      (fields (field (name "Manufacturer Part") "ECS-250-10-36Q-AES-TR") (field (name "Manufacturer") "ECS"))
      (libsource (lib "easyedapro") (part "ECS-250-10-36Q-AES-TR"))
    )
  )
  (nets
    (net (code "1") (name "DC_5V") (class "Default")
      (node (ref "H1") (pin "1") (pinfunction "1_1") (pintype "input"))
      (node (ref "P1") (pin "2") (pinfunction "2_2") (pintype "input"))
      (node (ref "R16") (pin "1") (pinfunction "1_1") (pintype "input"))
    )
    (net (code "2") (name "DC_12V") (class "Default")
      (node (ref "C25") (pin "1") (pinfunction "1_1") (pintype "input"))
      (node (ref "C27") (pin "1") (pinfunction "1_1") (pintype "input"))
      (node (ref "C28") (pin "2") (pinfunction "2_2") (pintype "input"))
      (node (ref "D11") (pin "2") (pinfunction "K_2") (pintype "input"))
      (node (ref "D12") (pin "1") (pinfunction "K_1") (pintype "unspecified"))
      (node (ref "D13") (pin "1") (pinfunction "K_1") (pintype "unspecified"))
      (node (ref "D3") (pin "1") (pinfunction "K_1") (pintype "unspecified"))
      (node (ref "D4") (pin "1") (pinfunction "K_1") (pintype "unspecified"))
      (node (ref "D5") (pin "1") (pinfunction "K_1") (pintype "unspecified"))
      (node (ref "D6") (pin "1") (pinfunction "K_1") (pintype "unspecified"))
      (node (ref "D7") (pin "1") (pinfunction "K_1") (pintype "unspecified"))
      (node (ref "RELAY1") (pin "1") (pinfunction "1_1") (pintype "input"))
      (node (ref "RELAY2") (pin "1") (pinfunction "1_1") (pintype "input"))
      (node (ref "RELAY3") (pin "1") (pinfunction "1_1") (pintype "input"))
      (node (ref "RELAY4") (pin "1") (pinfunction "1_1") (pintype "input"))
      (node (ref "RELAY5") (pin "1") (pinfunction "1_1") (pintype "input"))
      (node (ref "RELAY6") (pin "1") (pinfunction "1_1") (pintype "input"))
      (node (ref "RELAY7") (pin "1") (pinfunction "1_1") (pintype "input"))
      (node (ref "U30") (pin "3") (pinfunction "Vin_3") (pintype "input"))
    )
    (net (code "3") (name "GND") (class "Default")
      (node (ref "C1") (pin "2") (pinfunction "2_2") (pintype "input"))
      (node (ref "C17") (pin "2") (pinfunction "2_2") (pintype "input"))
      (node (ref "C18") (pin "1") (pinfunction "1_1") (pintype "input"))
      (node (ref "C19") (pin "2") (pinfunction "2_2") (pintype "input"))
      (node (ref "C2") (pin "1") (pinfunction "1_1") (pintype "input"))
      (node (ref "C20") (pin "1") (pinfunction "1_1") (pintype "input"))
      (node (ref "C21") (pin "2") (pinfunction "2_2") (pintype "input"))
      (node (ref "C22") (pin "1") (pinfunction "1_1") (pintype "input"))
      (node (ref "C23") (pin "2") (pinfunction "2_2") (pintype "input"))
      (node (ref "C24") (pin "1") (pinfunction "1_1") (pintype "input"))
      (node (ref "C25") (pin "2") (pinfunction "2_2") (pintype "input"))
      (node (ref "C26") (pin "1") (pinfunction "1_1") (pintype "input"))
      (node (ref "C27") (pin "2") (pinfunction "2_2") (pintype "input"))
      (node (ref "C28") (pin "1") (pinfunction "1_1") (pintype "input"))
      (node (ref "C3") (pin "2") (pinfunction "2_2") (pintype "input"))
      (node (ref "C4") (pin "1") (pinfunction "1_1") (pintype "input"))
      (node (ref "C5") (pin "1") (pinfunction "1_1") (pintype "input"))
      (node (ref "D1") (pin "2") (pinfunction "A_2") (pintype "input"))
      (node (ref "D2") (pin "2") (pinfunction "A_2") (pintype "input"))
      (node (ref "DC1") (pin "2") (pinfunction "2_2") (pintype "input"))
      (node (ref "DC1") (pin "3") (pinfunction "3_3") (pintype "input"))
      (node (ref "J2") (pin "1") (pinfunction "1_1") (pintype "input"))
      (node (ref "J3") (pin "1") (pinfunction "1_1") (pintype "input"))
      (node (ref "J4") (pin "1") (pinfunction "1_1") (pintype "input"))
      (node (ref "J5") (pin "1") (pinfunction "1_1") (pintype "input"))
      (node (ref "LED3") (pin "1") (pinfunction "C_1") (pintype "input"))
      (node (ref "P1") (pin "1") (pinfunction "1_1") (pintype "input"))
      (node (ref "Q1") (pin "2") (pinfunction "E_2") (pintype "input"))
      (node (ref "Q2") (pin "2") (pinfunction "E_2") (pintype "input"))
      (node (ref "Q3") (pin "2") (pinfunction "E_2") (pintype "input"))
      (node (ref "Q4") (pin "2") (pinfunction "E_2") (pintype "input"))
      (node (ref "Q5") (pin "2") (pinfunction "E_2") (pintype "input"))
      (node (ref "Q6") (pin "2") (pinfunction "E_2") (pintype "input"))
      (node (ref "Q7") (pin "2") (pinfunction "E_2") (pintype "input"))
      (node (ref "U1") (pin "1") (pinfunction "GND_1") (pintype "input"))
      (node (ref "U2") (pin "10") (pinfunction "10_10") (pintype "input"))
      (node (ref "U2") (pin "8") (pinfunction "8_8") (pintype "input"))
      (node (ref "U2") (pin "9") (pinfunction "9_9") (pintype "input"))
      (node (ref "U30") (pin "1") (pinfunction "GND_1") (pintype "input"))
      (node (ref "U6") (pin "23") (pinfunction "VSS_23") (pintype "input"))
      (node (ref "U6") (pin "47") (pinfunction "VSS_47") (pintype "input"))
      (node (ref "U6") (pin "8") (pinfunction "VSSA_8") (pintype "input"))
      (node (ref "X2") (pin "2") (pinfunction "2_2") (pintype "input"))
      (node (ref "X2") (pin "4") (pinfunction "4_4") (pintype "input"))
    )
    (net (code "4") (name "I2C_SCL") (class "Default")
      (node (ref "U6") (pin "35") (pinfunction "PF6/I2C1_SCL/I2C0_SCL_35") (pintype "input"))
    )
    (net (code "5") (name "I2C_SDA") (class "Default")
      (node (ref "U6") (pin "36") (pinfunction "PF7/I2C1_SDA/I2C0_SDA_36") (pintype "input"))
    )
    (net (code "6") (name "LDO_5V") (class "Default")
      (node (ref "C17") (pin "1") (pinfunction "1_1") (pintype "input"))
      (node (ref "C18") (pin "2") (pinfunction "2_2") (pintype "input"))
      (node (ref "C19") (pin "1") (pinfunction "1_1") (pintype "input"))
      (node (ref "C2") (pin "2") (pinfunction "2_2") (pintype "input"))
      (node (ref "C20") (pin "2") (pinfunction "2_2") (pintype "input"))
      (node (ref "C21") (pin "1") (pinfunction "1_1") (pintype "input"))
      (node (ref "C22") (pin "2") (pinfunction "2_2") (pintype "input"))
      (node (ref "C23") (pin "1") (pinfunction "1_1") (pintype "input"))
      (node (ref "C24") (pin "2") (pinfunction "2_2") (pintype "input"))
      (node (ref "C26") (pin "2") (pinfunction "2_2") (pintype "input"))
      (node (ref "C3") (pin "1") (pinfunction "1_1") (pintype "input"))
      (node (ref "D1") (pin "1") (pinfunction "K_1") (pintype "input"))
      (node (ref "LED1") (pin "2") (pinfunction "A_2") (pintype "input"))
      (node (ref "LED2") (pin "2") (pinfunction "A_2") (pintype "input"))
      (node (ref "LED4") (pin "2") (pinfunction "A_2") (pintype "input"))
      (node (ref "R6") (pin "2") (pinfunction "2_2") (pintype "input"))
      (node (ref "U1") (pin "16") (pinfunction "VCC_16") (pintype "input"))
      (node (ref "U2") (pin "1") (pinfunction "1_1") (pintype "input"))
      (node (ref "U30") (pin "4") (pinfunction "Vout_4") (pintype "input"))
      (node (ref "U6") (pin "1") (pinfunction "VDD_1") (pintype "input"))
      (node (ref "U6") (pin "24") (pinfunction "VDD_24") (pintype "input"))
      (node (ref "U6") (pin "48") (pinfunction "VDD_48") (pintype "input"))
      (node (ref "U6") (pin "9") (pinfunction "VDDA_9") (pintype "input"))
      (node (ref "USB1") (pin "1") (pinfunction "VBUS_1") (pintype "input"))
    )
    (net (code "7") (name "LED_BLUE") (class "Default")
      (node (ref "R7") (pin "1") (pinfunction "1_1") (pintype "input"))
      (node (ref "U6") (pin "3") (pinfunction "PC14_3") (pintype "input"))
    )
    (net (code "8") (name "LED_GREEN") (class "Default")
      (node (ref "R2") (pin "1") (pinfunction "1_1") (pintype "input"))
      (node (ref "U6") (pin "2") (pinfunction "PC13_2") (pintype "input"))
    )
    (net (code "9") (name "LED_RED") (class "Default")
      (node (ref "R1") (pin "1") (pinfunction "1_1") (pintype "input"))
      (node (ref "U6") (pin "4") (pinfunction "PC15_4") (pintype "input"))
    )
    (net (code "10") (name "MCO") (class "Default")
      (node (ref "U2") (pin "7") (pinfunction "7_7") (pintype "input"))
      (node (ref "U6") (pin "30") (pinfunction "PA9/CMP0_OUT/TIM1_CH2/UART1_TX/I2C1_SCL/MCO/TIM5_BKIN_30") (pintype "input"))
    )
    (net (code "11") (name "MCU_GET_SIGNAL") (class "Default")
      (node (ref "U6") (pin "29") (pinfunction "PA8/MCO/TIM1_CH1/CMP2_OUT_29") (pintype "input"))
    )
    (net (code "12") (name "Net-(D2-K)") (class "Default")
      (node (ref "D2") (pin "1") (pinfunction "K_1") (pintype "input"))
      (node (ref "USB1") (pin "4") (pinfunction "GND_4") (pintype "input"))
      (node (ref "USB1") (pin "5") (pinfunction "GND_5") (pintype "input"))
      (node (ref "USB1") (pin "6") (pinfunction "GND_6") (pintype "input"))
    )
    (net (code "13") (name "Net-(D3-A)") (class "Default")
      (node (ref "D3") (pin "2") (pinfunction "A_2") (pintype "unspecified"))
      (node (ref "Q1") (pin "3") (pinfunction "C_3") (pintype "input"))
      (node (ref "RELAY1") (pin "4") (pinfunction "4_4") (pintype "input"))
    )
    (net (code "14") (name "Net-(D4-A)") (class "Default")
      (node (ref "D4") (pin "2") (pinfunction "A_2") (pintype "unspecified"))
      (node (ref "Q2") (pin "3") (pinfunction "C_3") (pintype "input"))
      (node (ref "RELAY2") (pin "4") (pinfunction "4_4") (pintype "input"))
    )
    (net (code "15") (name "Net-(D5-A)") (class "Default")
      (node (ref "D5") (pin "2") (pinfunction "A_2") (pintype "unspecified"))
      (node (ref "Q3") (pin "3") (pinfunction "C_3") (pintype "input"))
      (node (ref "RELAY3") (pin "4") (pinfunction "4_4") (pintype "input"))
    )
    (net (code "16") (name "Net-(D6-A)") (class "Default")
      (node (ref "D6") (pin "2") (pinfunction "A_2") (pintype "unspecified"))
      (node (ref "Q4") (pin "3") (pinfunction "C_3") (pintype "input"))
      (node (ref "RELAY4") (pin "4") (pinfunction "4_4") (pintype "input"))
    )
    (net (code "17") (name "Net-(D7-A)") (class "Default")
      (node (ref "D7") (pin "2") (pinfunction "A_2") (pintype "unspecified"))
      (node (ref "Q5") (pin "3") (pinfunction "C_3") (pintype "input"))
      (node (ref "RELAY5") (pin "4") (pinfunction "4_4") (pintype "input"))
    )
    (net (code "18") (name "Net-(D11-A)") (class "Default")
      (node (ref "D11") (pin "1") (pinfunction "A_1") (pintype "input"))
      (node (ref "DC1") (pin "4") (pinfunction "4_4") (pintype "input"))
    )
    (net (code "19") (name "Net-(D12-A)") (class "Default")
      (node (ref "D12") (pin "2") (pinfunction "A_2") (pintype "unspecified"))
      (node (ref "Q6") (pin "3") (pinfunction "C_3") (pintype "input"))
      (node (ref "RELAY6") (pin "4") (pinfunction "4_4") (pintype "input"))
    )
    (net (code "20") (name "Net-(D13-A)") (class "Default")
      (node (ref "D13") (pin "2") (pinfunction "A_2") (pintype "unspecified"))
      (node (ref "Q7") (pin "3") (pinfunction "C_3") (pintype "input"))
      (node (ref "RELAY7") (pin "4") (pinfunction "4_4") (pintype "input"))
    )
    (net (code "21") (name "Net-(LED1-K)") (class "Default")
      (node (ref "LED1") (pin "1") (pinfunction "K_1") (pintype "input"))
      (node (ref "R1") (pin "2") (pinfunction "2_2") (pintype "input"))
    )
    (net (code "22") (name "Net-(LED2-C)") (class "Default")
      (node (ref "LED2") (pin "1") (pinfunction "C_1") (pintype "input"))
      (node (ref "R2") (pin "2") (pinfunction "2_2") (pintype "input"))
    )
    (net (code "23") (name "Net-(LED3-A)") (class "Default")
      (node (ref "LED3") (pin "2") (pinfunction "A_2") (pintype "input"))
      (node (ref "R6") (pin "1") (pinfunction "1_1") (pintype "input"))
    )
    (net (code "24") (name "Net-(LED4-C)") (class "Default")
      (node (ref "LED4") (pin "1") (pinfunction "C_1") (pintype "input"))
      (node (ref "R7") (pin "2") (pinfunction "2_2") (pintype "input"))
    )
    (net (code "25") (name "Net-(LED5-A)") (class "Default")
      (node (ref "LED5") (pin "2") (pinfunction "A_2") (pintype "input"))
      (node (ref "R8") (pin "2") (pinfunction "2_2") (pintype "input"))
    )
    (net (code "26") (name "Net-(LED5-C)") (class "Default")
      (node (ref "LED5") (pin "1") (pinfunction "C_1") (pintype "input"))
      (node (ref "Q1") (pin "1") (pinfunction "B_1") (pintype "input"))
    )
    (net (code "27") (name "Net-(LED6-A)") (class "Default")
      (node (ref "LED6") (pin "2") (pinfunction "A_2") (pintype "input"))
      (node (ref "R9") (pin "2") (pinfunction "2_2") (pintype "input"))
    )
    (net (code "28") (name "Net-(LED6-C)") (class "Default")
      (node (ref "LED6") (pin "1") (pinfunction "C_1") (pintype "input"))
      (node (ref "Q2") (pin "1") (pinfunction "B_1") (pintype "input"))
    )
    (net (code "29") (name "Net-(LED7-A)") (class "Default")
      (node (ref "LED7") (pin "2") (pinfunction "A_2") (pintype "input"))
      (node (ref "R10") (pin "2") (pinfunction "2_2") (pintype "input"))
    )
    (net (code "30") (name "Net-(LED7-C)") (class "Default")
      (node (ref "LED7") (pin "1") (pinfunction "C_1") (pintype "input"))
      (node (ref "Q3") (pin "1") (pinfunction "B_1") (pintype "input"))
    )
    (net (code "31") (name "Net-(LED8-A)") (class "Default")
      (node (ref "LED8") (pin "2") (pinfunction "A_2") (pintype "input"))
      (node (ref "R11") (pin "2") (pinfunction "2_2") (pintype "input"))
    )
    (net (code "32") (name "Net-(LED8-C)") (class "Default")
      (node (ref "LED8") (pin "1") (pinfunction "C_1") (pintype "input"))
      (node (ref "Q4") (pin "1") (pinfunction "B_1") (pintype "input"))
    )
    (net (code "33") (name "Net-(LED9-A)") (class "Default")
      (node (ref "LED9") (pin "2") (pinfunction "A_2") (pintype "input"))
      (node (ref "R12") (pin "2") (pinfunction "2_2") (pintype "input"))
    )
    (net (code "34") (name "Net-(LED9-C)") (class "Default")
      (node (ref "LED9") (pin "1") (pinfunction "C_1") (pintype "input"))
      (node (ref "Q5") (pin "1") (pinfunction "B_1") (pintype "input"))
    )
    (net (code "35") (name "Net-(LED10-A)") (class "Default")
      (node (ref "LED10") (pin "2") (pinfunction "A_2") (pintype "input"))
      (node (ref "R19") (pin "2") (pinfunction "2_2") (pintype "input"))
    )
    (net (code "36") (name "Net-(LED10-C)") (class "Default")
      (node (ref "LED10") (pin "1") (pinfunction "C_1") (pintype "input"))
      (node (ref "Q6") (pin "1") (pinfunction "B_1") (pintype "input"))
    )
    (net (code "37") (name "Net-(LED11-A)") (class "Default")
      (node (ref "LED11") (pin "2") (pinfunction "A_2") (pintype "input"))
      (node (ref "R20") (pin "2") (pinfunction "2_2") (pintype "input"))
    )
    (net (code "38") (name "Net-(LED11-C)") (class "Default")
      (node (ref "LED11") (pin "1") (pinfunction "C_1") (pintype "input"))
      (node (ref "Q7") (pin "1") (pinfunction "B_1") (pintype "input"))
    )
    (net (code "39") (name "Net-(RELAY2-Pad2)") (class "Default")
      (node (ref "RELAY2") (pin "2") (pinfunction "2_2") (pintype "input"))
      (node (ref "U21") (pin "1") (pinfunction "1_1") (pintype "unspecified"))
    )
    (net (code "40") (name "Net-(RELAY3-Pad2)") (class "Default")
      (node (ref "RELAY3") (pin "2") (pinfunction "2_2") (pintype "input"))
      (node (ref "U23") (pin "1") (pinfunction "1_1") (pintype "unspecified"))
    )
    (net (code "41") (name "Net-(RELAY4-Pad2)") (class "Default")
      (node (ref "RELAY4") (pin "2") (pinfunction "2_2") (pintype "input"))
      (node (ref "U25") (pin "1") (pinfunction "1_1") (pintype "unspecified"))
    )
    (net (code "42") (name "Net-(RELAY5-Pad2)") (class "Default")
      (node (ref "RELAY5") (pin "2") (pinfunction "2_2") (pintype "input"))
      (node (ref "U27") (pin "1") (pinfunction "1_1") (pintype "unspecified"))
    )
    (net (code "43") (name "Net-(RELAY6-Pad2)") (class "Default")
      (node (ref "RELAY6") (pin "2") (pinfunction "2_2") (pintype "input"))
      (node (ref "U31") (pin "1") (pinfunction "1_1") (pintype "unspecified"))
    )
    (net (code "44") (name "Net-(RELAY7-Pad2)") (class "Default")
      (node (ref "RELAY7") (pin "2") (pinfunction "2_2") (pintype "input"))
      (node (ref "U33") (pin "1") (pinfunction "1_1") (pintype "unspecified"))
    )
    (net (code "45") (name "Net-(U1-V3)") (class "Default")
      (node (ref "C1") (pin "1") (pinfunction "1_1") (pintype "input"))
      (node (ref "U1") (pin "4") (pinfunction "V3_4") (pintype "input"))
    )
    (net (code "46") (name "Net-(U1-XI)") (class "Default")
      (node (ref "C4") (pin "2") (pinfunction "2_2") (pintype "input"))
      (node (ref "U1") (pin "7") (pinfunction "XI_7") (pintype "input"))
      (node (ref "X1") (pin "1") (pinfunction "OSC1_1") (pintype "input"))
    )
    (net (code "47") (name "Net-(U1-XO)") (class "Default")
      (node (ref "C5") (pin "2") (pinfunction "2_2") (pintype "input"))
      (node (ref "U1") (pin "8") (pinfunction "XO_8") (pintype "input"))
      (node (ref "X1") (pin "2") (pinfunction "OSC2_2") (pintype "input"))
    )
    (net (code "48") (name "OSC_IN") (class "Default")
      (node (ref "U6") (pin "5") (pinfunction "PF0/OSC_IN/I2C0_SDA_5") (pintype "input"))
      (node (ref "X2") (pin "1") (pinfunction "OSC1_1") (pintype "input"))
    )
    (net (code "49") (name "OSC_OUT") (class "Default")
      (node (ref "U6") (pin "6") (pinfunction "PF1/OSC_OUT/I2C0_SCL_6") (pintype "input"))
      (node (ref "X2") (pin "3") (pinfunction "OSC2_3") (pintype "input"))
    )
    (net (code "50") (name "RLY1_CTRL") (class "Default")
      (node (ref "R8") (pin "1") (pinfunction "1_1") (pintype "input"))
      (node (ref "U6") (pin "19") (pinfunction "PB1/IR_TXD/TIM1_3N/ADC_IN8_19") (pintype "input"))
    )
    (net (code "51") (name "RLY1_IN") (class "Default")
      (node (ref "H1") (pin "2") (pinfunction "2_2") (pintype "input"))
      (node (ref "R16") (pin "2") (pinfunction "2_2") (pintype "input"))
      (node (ref "RELAY1") (pin "5") (pinfunction "5_5") (pintype "input"))
    )
    (net (code "52") (name "RLY2_CTRL") (class "Default")
      (node (ref "R9") (pin "1") (pinfunction "1_1") (pintype "input"))
      (node (ref "U6") (pin "44") (pinfunction "PB2/BEEP1/MCO/CMP1_OUT/ADC_IN9_44") (pintype "input"))
    )
    (net (code "53") (name "RLY3_CTRL") (class "Default")
      (node (ref "R10") (pin "1") (pinfunction "1_1") (pintype "input"))
      (node (ref "U6") (pin "39") (pinfunction "PB3/SPI1_SCK/ADC_IN10/CMP0_N_39") (pintype "input"))
    )
    (net (code "54") (name "RLY4_CTRL") (class "Default")
      (node (ref "R11") (pin "1") (pinfunction "1_1") (pintype "input"))
      (node (ref "U6") (pin "40") (pinfunction "PB4/SPI1_MISO/CMP0_OUT/TIM7_BKIN/ADC_IN11_40") (pintype "input"))
    )
    (net (code "55") (name "RLY5_CTRL") (class "Default")
      (node (ref "R12") (pin "1") (pinfunction "1_1") (pintype "input"))
      (node (ref "R19") (pin "1") (pinfunction "1_1") (pintype "input"))
      (node (ref "R20") (pin "1") (pinfunction "1_1") (pintype "input"))
      (node (ref "U6") (pin "41") (pinfunction "PB5/SPI1_MOSI/TIM6_BKIN/ADC_IN13/CMP2_N_41") (pintype "input"))
    )
    (net (code "56") (name "RLY6_CTRL") (class "Default")
      (node (ref "U6") (pin "42") (pinfunction "PB6/I2C1_SCL/UART1_TX/UART0_TX/I2C0_SCL/TIM6_CH1N/ADC_IN14/CMP2_N_42") (pintype "input"))
    )
    (net (code "57") (name "RLY7_CTRL") (class "Default")
      (node (ref "U6") (pin "43") (pinfunction "PB7/I2C1_SDA/UART1_RX/UART0_RX/I2C0_SDA/CMP2_OUT/TIM7/CJ1N/ADC_IN15_43") (pintype "input"))
    )
    (net (code "58") (name "RLY8_CTRL") (class "Default")
      (node (ref "U6") (pin "45") (pinfunction "PB8/I2C0_SCL/TIM6_CH1/CMP2_P1_45") (pintype "input"))
    )
    (net (code "59") (name "RSTN") (class "Default")
      (node (ref "U2") (pin "6") (pinfunction "6_6") (pintype "input"))
      (node (ref "U6") (pin "7") (pinfunction "NRST_7") (pintype "input"))
    )
    (net (code "60") (name "SWCLK") (class "Default")
      (node (ref "U2") (pin "3") (pinfunction "3_3") (pintype "input"))
      (node (ref "U6") (pin "37") (pinfunction "PA14/SWCLK/UART1_TX/UART0_TX_37") (pintype "input"))
    )
    (net (code "61") (name "SWDIO") (class "Default")
      (node (ref "U2") (pin "2") (pinfunction "2_2") (pintype "input"))
      (node (ref "U6") (pin "34") (pinfunction "PA13/SWDIO/IR_TXD_34") (pintype "input"))
    )
    (net (code "62") (name "UART_RX") (class "Default")
      (node (ref "U1") (pin "2") (pinfunction "TXD_2") (pintype "input"))
      (node (ref "U2") (pin "5") (pinfunction "5_5") (pintype "input"))
      (node (ref "U6") (pin "13") (pinfunction "PA3/UART0_RX/UART1_RX/ADC_IN3/OPA0_P_13") (pintype "input"))
    )
    (net (code "63") (name "UART_TX") (class "Default")
      (node (ref "U1") (pin "3") (pinfunction "RXD_3") (pintype "input"))
      (node (ref "U2") (pin "4") (pinfunction "4_4") (pintype "input"))
      (node (ref "U6") (pin "12") (pinfunction "PA2/UART0_TX/UART1_TX/TIM5_CH1/ADC_IN2/CMP2_P3/OPA1_OUT_12") (pintype "input"))
    )
    (net (code "64") (name "USB_D+") (class "Default")
      (node (ref "U1") (pin "5") (pinfunction "UD+_5") (pintype "input"))
      (node (ref "USB1") (pin "3") (pinfunction "D+_3") (pintype "input"))
    )
    (net (code "65") (name "USB_D-") (class "Default")
      (node (ref "U1") (pin "6") (pinfunction "UD-_6") (pintype "input"))
      (node (ref "USB1") (pin "2") (pinfunction "D-_2") (pintype "input"))
    )
    (net (code "66") (name "unconnected-(RELAY1-Pad2)") (class "Default")
      (node (ref "RELAY1") (pin "2") (pinfunction "2_2") (pintype "input"))
    )
    (net (code "67") (name "unconnected-(RELAY1-Pad3)") (class "Default")
      (node (ref "RELAY1") (pin "3") (pinfunction "3_3") (pintype "input+no_connect"))
    )
    (net (code "68") (name "unconnected-(RELAY2-Pad3)") (class "Default")
      (node (ref "RELAY2") (pin "3") (pinfunction "3_3") (pintype "input+no_connect"))
    )
    (net (code "69") (name "unconnected-(RELAY2-Pad5)") (class "Default")
      (node (ref "RELAY2") (pin "5") (pinfunction "5_5") (pintype "input"))
    )
    (net (code "70") (name "unconnected-(RELAY3-Pad3)") (class "Default")
      (node (ref "RELAY3") (pin "3") (pinfunction "3_3") (pintype "input+no_connect"))
    )
    (net (code "71") (name "unconnected-(RELAY3-Pad5)") (class "Default")
      (node (ref "RELAY3") (pin "5") (pinfunction "5_5") (pintype "input"))
    )
    (net (code "72") (name "unconnected-(RELAY4-Pad3)") (class "Default")
      (node (ref "RELAY4") (pin "3") (pinfunction "3_3") (pintype "input+no_connect"))
    )
    (net (code "73") (name "unconnected-(RELAY4-Pad5)") (class "Default")
      (node (ref "RELAY4") (pin "5") (pinfunction "5_5") (pintype "input"))
    )
    (net (code "74") (name "unconnected-(RELAY5-Pad3)") (class "Default")
      (node (ref "RELAY5") (pin "3") (pinfunction "3_3") (pintype "input+no_connect"))
    )
    (net (code "75") (name "unconnected-(RELAY5-Pad5)") (class "Default")
      (node (ref "RELAY5") (pin "5") (pinfunction "5_5") (pintype "input"))
    )
    (net (code "76") (name "unconnected-(RELAY6-Pad3)") (class "Default")
      (node (ref "RELAY6") (pin "3") (pinfunction "3_3") (pintype "input+no_connect"))
    )
    (net (code "77") (name "unconnected-(RELAY6-Pad5)") (class "Default")
      (node (ref "RELAY6") (pin "5") (pinfunction "5_5") (pintype "input"))
    )
    (net (code "78") (name "unconnected-(RELAY7-Pad3)") (class "Default")
      (node (ref "RELAY7") (pin "3") (pinfunction "3_3") (pintype "input+no_connect"))
    )
    (net (code "79") (name "unconnected-(RELAY7-Pad5)") (class "Default")
      (node (ref "RELAY7") (pin "5") (pinfunction "5_5") (pintype "input"))
    )
    (net (code "80") (name "unconnected-(U1-CTS#-Pad9)") (class "Default")
      (node (ref "U1") (pin "9") (pinfunction "CTS#_9") (pintype "input+no_connect"))
    )
    (net (code "81") (name "unconnected-(U1-DCD#-Pad12)") (class "Default")
      (node (ref "U1") (pin "12") (pinfunction "DCD#_12") (pintype "input+no_connect"))
    )
    (net (code "82") (name "unconnected-(U1-DSR#-Pad10)") (class "Default")
      (node (ref "U1") (pin "10") (pinfunction "DSR#_10") (pintype "input+no_connect"))
    )
    (net (code "83") (name "unconnected-(U1-DTR#-Pad13)") (class "Default")
      (node (ref "U1") (pin "13") (pinfunction "DTR#_13") (pintype "input+no_connect"))
    )
    (net (code "84") (name "unconnected-(U1-R232-Pad15)") (class "Default")
      (node (ref "U1") (pin "15") (pinfunction "R232_15") (pintype "input+no_connect"))
    )
    (net (code "85") (name "unconnected-(U1-RI#-Pad11)") (class "Default")
      (node (ref "U1") (pin "11") (pinfunction "RI#_11") (pintype "input+no_connect"))
    )
    (net (code "86") (name "unconnected-(U1-RTS#-Pad14)") (class "Default")
      (node (ref "U1") (pin "14") (pinfunction "RTS#_14") (pintype "input+no_connect"))
    )
    (net (code "87") (name "unconnected-(U6-PA0{slash}ADC_IN0{slash}VREF+{slash}CMP1_P{slash}OPA1_P-Pad10)") (class "Default")
      (node (ref "U6") (pin "10") (pinfunction "PA0/ADC_IN0/VREF+/CMP1_P/OPA1_P_10") (pintype "input+no_connect"))
    )
    (net (code "88") (name "unconnected-(U6-PA1{slash}ADC_IN1{slash}CMP1_N{slash}OPA1_N-Pad11)") (class "Default")
      (node (ref "U6") (pin "11") (pinfunction "PA1/ADC_IN1/CMP1_N/OPA1_N_11") (pintype "input+no_connect"))
    )
    (net (code "89") (name "unconnected-(U6-PA4{slash}SPI0_CS{slash}UART1_TX{slash}UART0_TX-Pad14)") (class "Default")
      (node (ref "U6") (pin "14") (pinfunction "PA4/SPI0_CS/UART1_TX/UART0_TX_14") (pintype "input+no_connect"))
    )
    (net (code "90") (name "unconnected-(U6-PA5{slash}SPI0_SCK{slash}UART1_RX{slash}UART0_RX{slash}ADC_IN5{slash}CMP0_P3{slash}OPA0_OUT-Pad15)") (class "Default")
      (node (ref "U6") (pin "15") (pinfunction "PA5/SPI0_SCK/UART1_RX/UART0_RX/ADC_IN5/CMP0_P3/OPA0_OUT_15") (pintype "input+no_connect"))
    )
    (net (code "91") (name "unconnected-(U6-PA6{slash}SPI0_MISO{slash}TIM1_BKIN{slash}TIM6{slash}CH1{slash}ADC_IN6-Pad16)") (class "Default")
      (node (ref "U6") (pin "16") (pinfunction "PA6/SPI0_MISO/TIM1_BKIN/TIM6/CH1/ADC_IN6_16") (pintype "input+no_connect"))
    )
    (net (code "92") (name "unconnected-(U6-PA7{slash}SPI0_MOSI{slash}TIM1_CJ1N{slash}ADC_ETR{slash}TIM7_CH1{slash}ADC_IN7-Pad17)") (class "Default")
      (node (ref "U6") (pin "17") (pinfunction "PA7/SPI0_MOSI/TIM1_CJ1N/ADC_ETR/TIM7_CH1/ADC_IN7_17") (pintype "input+no_connect"))
    )
    (net (code "93") (name "unconnected-(U6-PA10{slash}CMP1_OUT{slash}TIM1_CH3{slash}UART1_RX{slash}I2C1_SDA{slash}TIM7_BKIN-Pad31)") (class "Default")
      (node (ref "U6") (pin "31") (pinfunction "PA10/CMP1_OUT/TIM1_CH3/UART1_RX/I2C1_SDA/TIM7_BKIN_31") (pintype "input+no_connect"))
    )
    (net (code "94") (name "unconnected-(U6-PA11{slash}I2C1_SCL{slash}TIM1_CH4{slash}I2C0_SCL-Pad32)") (class "Default")
      (node (ref "U6") (pin "32") (pinfunction "PA11/I2C1_SCL/TIM1_CH4/I2C0_SCL_32") (pintype "input+no_connect"))
    )
    (net (code "95") (name "unconnected-(U6-PA12{slash}I2C1_SDA{slash}TIM1_CH4N{slash}I2C0_SDA{slash}TIM1_ETR-Pad33)") (class "Default")
      (node (ref "U6") (pin "33") (pinfunction "PA12/I2C1_SDA/TIM1_CH4N/I2C0_SDA/TIM1_ETR_33") (pintype "input+no_connect"))
    )
    (net (code "96") (name "unconnected-(U6-PA15{slash}SPI1_CS{slash}UART1_RX{slash}UART0_RX{slash}CMP0_P0-Pad38)") (class "Default")
      (node (ref "U6") (pin "38") (pinfunction "PA15/SPI1_CS/UART1_RX/UART0_RX/CMP0_P0_38") (pintype "input+no_connect"))
    )
    (net (code "97") (name "unconnected-(U6-PB0{slash}TIM1_CH2N{slash}ADC_IN12-Pad18)") (class "Default")
      (node (ref "U6") (pin "18") (pinfunction "PB0/TIM1_CH2N/ADC_IN12_18") (pintype "input+no_connect"))
    )
    (net (code "98") (name "unconnected-(U6-PB9{slash}IR_TXD{slash}I2C0_SDA{slash}TIM7_CH1{slash}CMP2_P2-Pad46)") (class "Default")
      (node (ref "U6") (pin "46") (pinfunction "PB9/IR_TXD/I2C0_SDA/TIM7_CH1/CMP2_P2_46") (pintype "input+no_connect"))
    )
    (net (code "99") (name "unconnected-(U6-PB10{slash}SPI1_SCK{slash}I2C0_SCL{slash}I2C1_SCL{slash}TIM6_CH1{slash}CMP_P1-Pad21)") (class "Default")
      (node (ref "U6") (pin "21") (pinfunction "PB10/SPI1_SCK/I2C0_SCL/I2C1_SCL/TIM6_CH1/CMP_P1_21") (pintype "input+no_connect"))
    )
    (net (code "100") (name "unconnected-(U6-PB11{slash}I2C0_SDA{slash}I2C1_SDA{slash}TIM7_CH1{slash}CMP0_P2-Pad22)") (class "Default")
      (node (ref "U6") (pin "22") (pinfunction "PB11/I2C0_SDA/I2C1_SDA/TIM7_CH1/CMP0_P2_22") (pintype "input+no_connect"))
    )
    (net (code "101") (name "unconnected-(U6-PB12{slash}SPI0_CS{slash}TIM1_BKIN{slash}SPI1_CS-Pad25)") (class "Default")
      (node (ref "U6") (pin "25") (pinfunction "PB12/SPI0_CS/TIM1_BKIN/SPI1_CS_25") (pintype "input+no_connect"))
    )
    (net (code "102") (name "unconnected-(U6-PB13{slash}SPI0_SCK{slash}TIM1_CH1N{slash}SPI1_SCK{slash}I2C1_SDA-Pad26)") (class "Default")
      (node (ref "U6") (pin "26") (pinfunction "PB13/SPI0_SCK/TIM1_CH1N/SPI1_SCK/I2C1_SDA_26") (pintype "input+no_connect"))
    )
    (net (code "103") (name "unconnected-(U6-PB14{slash}SPI0_MISO{slash}TIM1_CH2N{slash}SPI1_MISO{slash}TIM5_CH1-Pad27)") (class "Default")
      (node (ref "U6") (pin "27") (pinfunction "PB14/SPI0_MISO/TIM1_CH2N/SPI1_MISO/TIM5_CH1_27") (pintype "input+no_connect"))
    )
    (net (code "104") (name "unconnected-(U6-PB15{slash}SPI0_MOSI{slash}TIM1_CH3N{slash}SPI1_MOSI{slash}TIM5_CH1N-Pad28)") (class "Default")
      (node (ref "U6") (pin "28") (pinfunction "PB15/SPI0_MOSI/TIM1_CH3N/SPI1_MOSI/TIM5_CH1N_28") (pintype "input+no_connect"))
    )
    (net (code "105") (name "unconnected-(U6-PF2{slash}TIM5_CH1-Pad20)") (class "Default")
      (node (ref "U6") (pin "20") (pinfunction "PF2/TIM5_CH1_20") (pintype "input+no_connect"))
    )
    (net (code "106") (name "unconnected-(U22-Pad1)") (class "Default")
      (node (ref "U22") (pin "1") (pinfunction "1_1") (pintype "unspecified"))
    )
    (net (code "107") (name "unconnected-(U24-Pad1)") (class "Default")
      (node (ref "U24") (pin "1") (pinfunction "1_1") (pintype "unspecified"))
    )
    (net (code "108") (name "unconnected-(U26-Pad1)") (class "Default")
      (node (ref "U26") (pin "1") (pinfunction "1_1") (pintype "unspecified"))
    )
    (net (code "109") (name "unconnected-(U28-Pad1)") (class "Default")
      (node (ref "U28") (pin "1") (pinfunction "1_1") (pintype "unspecified"))
    )
    (net (code "110") (name "unconnected-(U30-Vout-Pad2)") (class "Default")
      (node (ref "U30") (pin "2") (pinfunction "Vout_2") (pintype "input+no_connect"))
    )
    (net (code "111") (name "unconnected-(U32-Pad1)") (class "Default")
      (node (ref "U32") (pin "1") (pinfunction "1_1") (pintype "unspecified"))
    )
    (net (code "112") (name "unconnected-(U34-Pad1)") (class "Default")
      (node (ref "U34") (pin "1") (pinfunction "1_1") (pintype "unspecified"))
    )
  )
)
